# Maduino_Zero_Lorawan_Node_v1_0.net
KiCad netlist of a schematic drawn in EAGLE
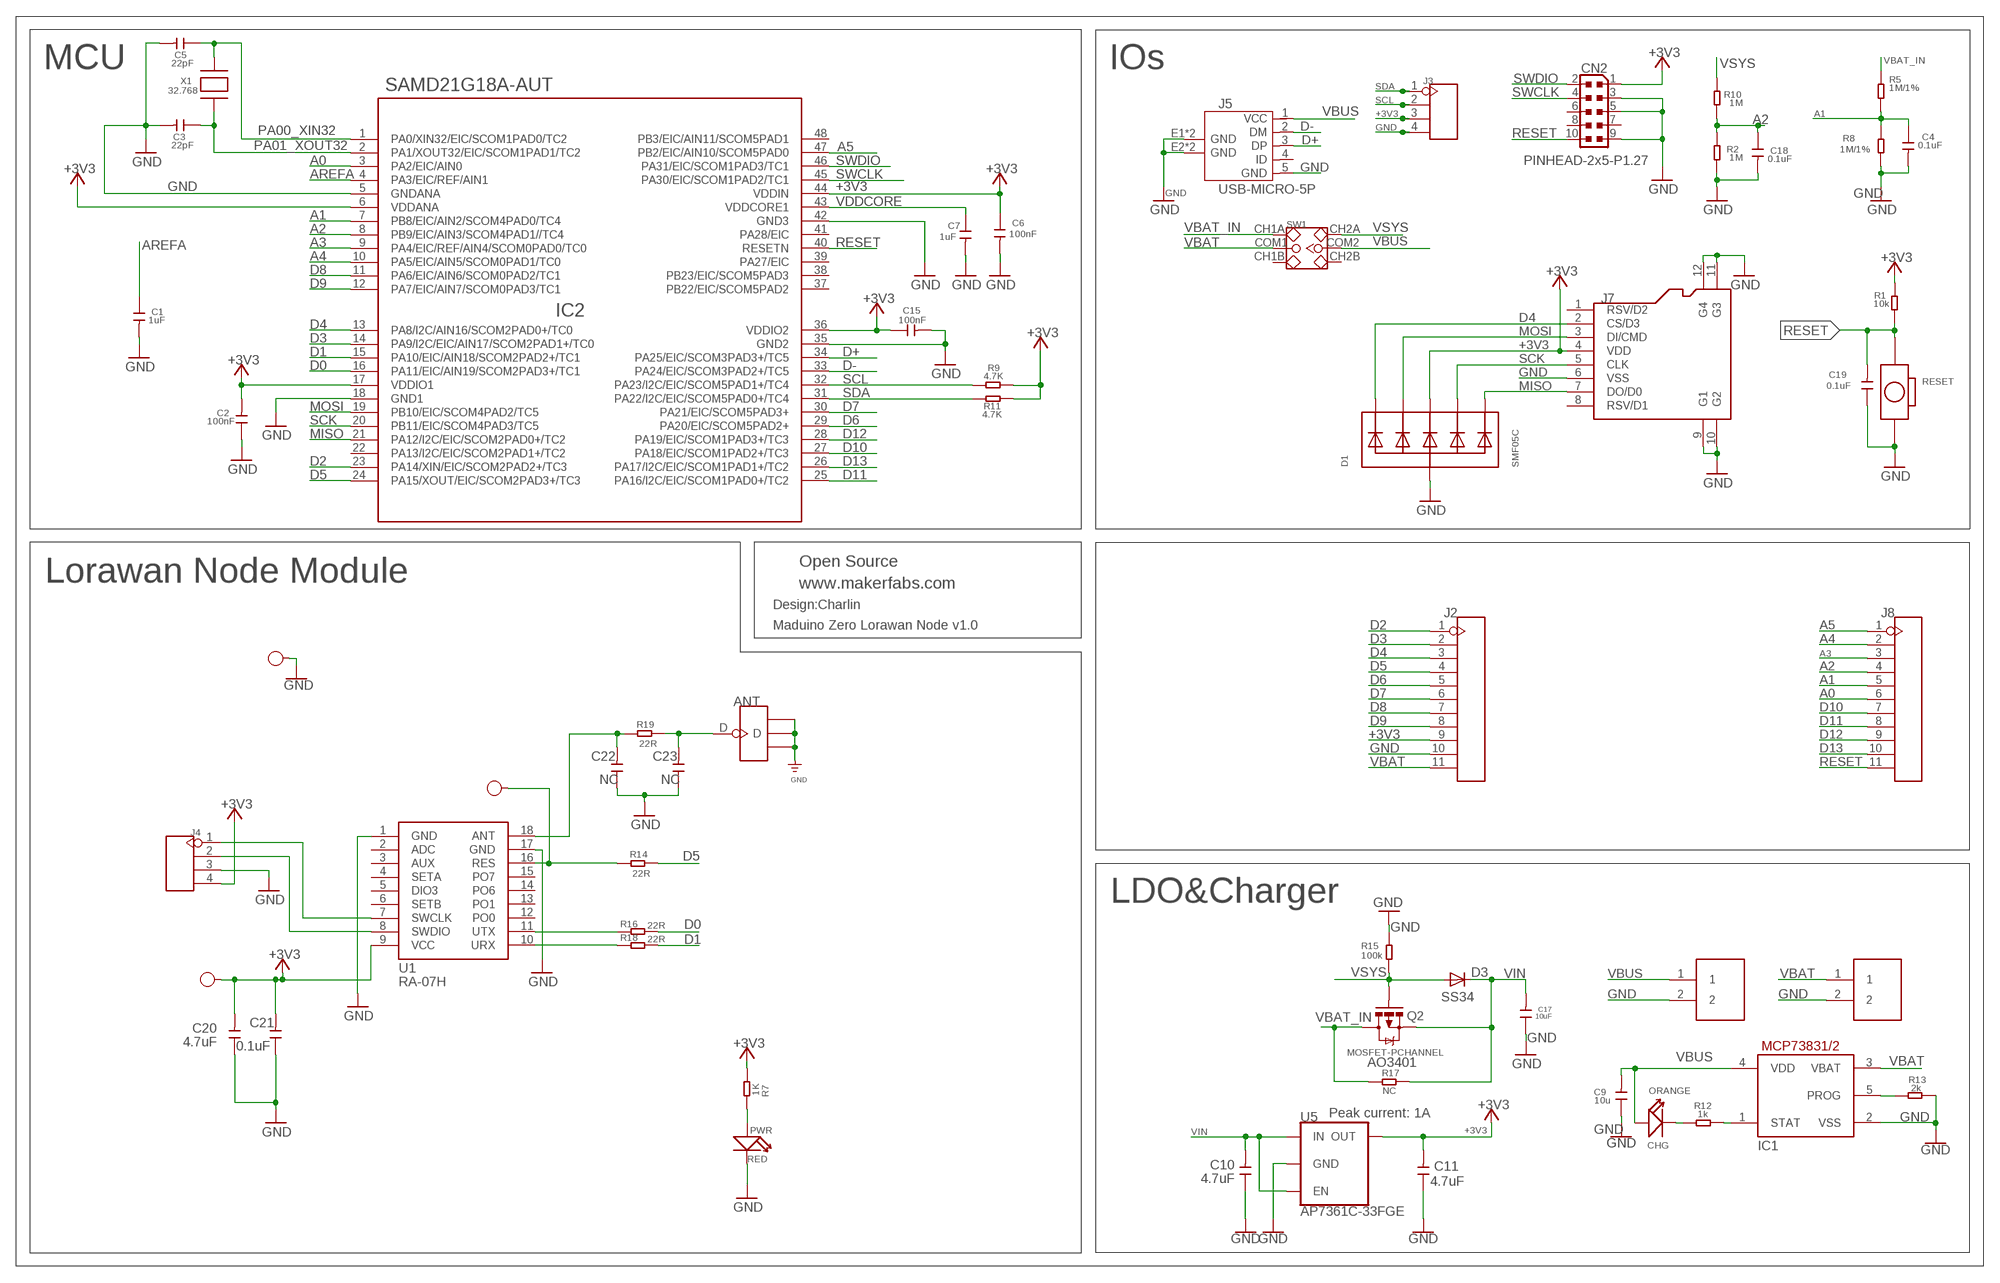
[diagram p0: schematic, sheet 1]

(export (version "E")
  (design (tool "Eeschema 10.0.6"))
  (components
    (comp (ref "3V3")
      (value "TEST-POINT'4545'")
      (footprint "eagle-import:TP-D45MIL")
      (fields (field (name "PARTNO") "DNP") (field (name "PARTNO_1") "DNP"))
      (libsource (lib "eagle-import") (part "TEST-POINT'4545'"))
    )
    (comp (ref "ANT")
      (value "ANTENNA-U-FL")
      (footprint "eagle-import:4P-U-FL")
      (libsource (lib "eagle-import") (part "ANTENNA-U-FL"))
    )
    (comp (ref "C1")
      (value "1uF")
      (footprint "eagle-import:C0603")
      (libsource (lib "eagle-import") (part "C-0603"))
    )
    (comp (ref "C2")
      (value "100nF")
      (footprint "eagle-import:C0603")
      (libsource (lib "eagle-import") (part "C-0603"))
    )
    (comp (ref "C3")
      (value "22pF")
      (footprint "eagle-import:C0603")
      (libsource (lib "eagle-import") (part "C-0603"))
    )
    (comp (ref "C4")
      (value "0.1uF")
      (footprint "eagle-import:C0603")
      (libsource (lib "eagle-import") (part "C-0603"))
    )
    (comp (ref "C5")
      (value "22pF")
      (footprint "eagle-import:C0603")
      (libsource (lib "eagle-import") (part "C-0603"))
    )
    (comp (ref "C6")
      (value "100nF")
      (footprint "eagle-import:C0603")
      (libsource (lib "eagle-import") (part "C-0603"))
    )
    (comp (ref "C7")
      (value "1uF")
      (footprint "eagle-import:C0603")
      (libsource (lib "eagle-import") (part "C-0603"))
    )
    (comp (ref "C9")
      (value "10u")
      (footprint "eagle-import:C0603")
      (libsource (lib "eagle-import") (part "C-0603"))
    )
    (comp (ref "C10")
      (value "4.7uF")
      (footprint "eagle-import:C0603")
      (libsource (lib "eagle-import") (part "C-0603"))
    )
    (comp (ref "C11")
      (value "4.7uF")
      (footprint "eagle-import:C0603")
      (libsource (lib "eagle-import") (part "C-0603"))
    )
    (comp (ref "C15")
      (value "100nF")
      (footprint "eagle-import:C0603")
      (libsource (lib "eagle-import") (part "C-0603"))
    )
    (comp (ref "C17")
      (value "10uF")
      (footprint "eagle-import:C0603")
      (libsource (lib "eagle-import") (part "C-0603"))
    )
    (comp (ref "C18")
      (value "0.1uF")
      (footprint "eagle-import:C0603")
      (libsource (lib "eagle-import") (part "C-0603"))
    )
    (comp (ref "C19")
      (value "0.1uF")
      (footprint "eagle-import:C0603")
      (libsource (lib "eagle-import") (part "C-0603"))
    )
    (comp (ref "C20")
      (value "4.7uF")
      (footprint "eagle-import:C0603")
      (libsource (lib "eagle-import") (part "C-0603"))
    )
    (comp (ref "C21")
      (value "0.1uF")
      (footprint "eagle-import:C0603")
      (libsource (lib "eagle-import") (part "C-0603"))
    )
    (comp (ref "C22")
      (value "NC")
      (footprint "eagle-import:C0603")
      (libsource (lib "eagle-import") (part "C-0603"))
    )
    (comp (ref "C23")
      (value "NC")
      (footprint "eagle-import:C0603")
      (libsource (lib "eagle-import") (part "C-0603"))
    )
    (comp (ref "CHG")
      (value "ORANGE")
      (footprint "eagle-import:D0603")
      (libsource (lib "eagle-import") (part "007-LED0603"))
    )
    (comp (ref "CN2")
      (value "PINHEAD-2x5-P1.27")
      (footprint "eagle-import:PINHEAD_2X05_127")
      (libsource (lib "eagle-import") (part "0171_PH127-205DF055G00AROUND-PADS"))
    )
    (comp (ref "D1")
      (value "SMF05C")
      (footprint "eagle-import:SOT363")
      (libsource (lib "eagle-import") (part "TVSARRAY_5LANE"))
    )
    (comp (ref "D3")
      (value "SS34")
      (footprint "eagle-import:DO-214AC")
      (libsource (lib "eagle-import") (part "DIODE-DO-214AC"))
    )
    (comp (ref "GND")
      (value "TEST-POINT'4545'")
      (footprint "eagle-import:TP-D45MIL")
      (fields (field (name "PARTNO") "DNP"))
      (libsource (lib "eagle-import") (part "TEST-POINT'4545'"))
    )
    (comp (ref "IC1")
      (value "MCP73831/OT")
      (footprint "eagle-import:SOT23-5L")
      (libsource (lib "eagle-import") (part "MCP73831/OT"))
    )
    (comp (ref "IC2")
      (value "SAMD21G18A-AUT")
      (footprint "eagle-import:TQFP48-7X7")
      (libsource (lib "eagle-import") (part "ATSAMD21G18A-AUT"))
    )
    (comp (ref "J1")
      (value "PH2.0-2P-90-DIP")
      (footprint "eagle-import:PH2.0-2P-90-DIP")
      (libsource (lib "eagle-import") (part "PH2.0-2P-90-DIP"))
    )
    (comp (ref "J2")
      (value "HEADER-11P-2.54")
      (footprint "eagle-import:11P-2.54")
      (libsource (lib "eagle-import") (part "HEADER-11P-2.54"))
    )
    (comp (ref "J3")
      (value "HEADER-4P-60/35MILROUND")
      (footprint "eagle-import:4P-65_35ROUND")
      (libsource (lib "eagle-import") (part "HEADER-4P-60/35MILROUND"))
    )
    (comp (ref "J4")
      (value "HEADER-4P-60/35MILROUND")
      (footprint "eagle-import:4P-65_35ROUND")
      (libsource (lib "eagle-import") (part "HEADER-4P-60/35MILROUND"))
    )
    (comp (ref "J5")
      (value "USB-MICRO-5P")
      (footprint "eagle-import:MICRO-USB-5P")
      (libsource (lib "eagle-import") (part "USB-MICRO-5P"))
    )
    (comp (ref "J6")
      (value "PH2.0-2P-90-DIP")
      (footprint "eagle-import:PH2.0-2P-90-DIP")
      (libsource (lib "eagle-import") (part "PH2.0-2P-90-DIP"))
    )
    (comp (ref "J7")
      (value "HOLDER-MICROSD-8P")
      (footprint "eagle-import:8P-SMD")
      (libsource (lib "eagle-import") (part "HOLDER-MICROSD-8P"))
    )
    (comp (ref "J8")
      (value "HEADER-11P-2.54")
      (footprint "eagle-import:11P-2.54")
      (libsource (lib "eagle-import") (part "HEADER-11P-2.54"))
    )
    (comp (ref "PWR")
      (value "RED")
      (footprint "eagle-import:LED-0603")
      (libsource (lib "eagle-import") (part "LED'0603'"))
    )
    (comp (ref "Q2")
      (value "MOSFET-PCHANNEL")
      (footprint "eagle-import:SOT23-3")
      (libsource (lib "eagle-import") (part "MOSFET-PCHANNEL"))
    )
    (comp (ref "R1")
      (value "10k")
      (footprint "eagle-import:R0603")
      (libsource (lib "eagle-import") (part "R-0603"))
    )
    (comp (ref "R2")
      (value "1M")
      (footprint "eagle-import:R0603")
      (libsource (lib "eagle-import") (part "R-0603"))
    )
    (comp (ref "R5")
      (value "1M/1%")
      (footprint "eagle-import:R0603")
      (libsource (lib "eagle-import") (part "R-0603"))
    )
    (comp (ref "R7")
      (value "1K")
      (footprint "eagle-import:R0603")
      (libsource (lib "eagle-import") (part "R-0603"))
    )
    (comp (ref "R8")
      (value "1M/1%")
      (footprint "eagle-import:R0603")
      (libsource (lib "eagle-import") (part "R-0603"))
    )
    (comp (ref "R9")
      (value "4.7K")
      (footprint "eagle-import:R0603")
      (libsource (lib "eagle-import") (part "R-0603"))
    )
    (comp (ref "R10")
      (value "1M")
      (footprint "eagle-import:R0603")
      (libsource (lib "eagle-import") (part "R-0603"))
    )
    (comp (ref "R11")
      (value "4.7K")
      (footprint "eagle-import:R0603")
      (libsource (lib "eagle-import") (part "R-0603"))
    )
    (comp (ref "R12")
      (value "1k")
      (footprint "eagle-import:R0603")
      (libsource (lib "eagle-import") (part "R-0603"))
    )
    (comp (ref "R13")
      (value "2k")
      (footprint "eagle-import:R0603")
      (libsource (lib "eagle-import") (part "R-0603"))
    )
    (comp (ref "R14")
      (value "22R")
      (footprint "eagle-import:R0603")
      (libsource (lib "eagle-import") (part "R-0603"))
    )
    (comp (ref "R15")
      (value "100k")
      (footprint "eagle-import:R0603")
      (libsource (lib "eagle-import") (part "R-0603"))
    )
    (comp (ref "R16")
      (value "22R")
      (footprint "eagle-import:R0603")
      (libsource (lib "eagle-import") (part "R-0603"))
    )
    (comp (ref "R17")
      (value "NC")
      (footprint "eagle-import:R0603")
      (libsource (lib "eagle-import") (part "R-0603"))
    )
    (comp (ref "R18")
      (value "22R")
      (footprint "eagle-import:R0603")
      (libsource (lib "eagle-import") (part "R-0603"))
    )
    (comp (ref "R19")
      (value "22R")
      (footprint "eagle-import:R0603")
      (libsource (lib "eagle-import") (part "R-0603"))
    )
    (comp (ref "RES")
      (value "TEST-POINT'4545'")
      (footprint "eagle-import:TP-D45MIL")
      (fields (field (name "PARTNO") "DNP") (field (name "PARTNO_1") "DNP"))
      (libsource (lib "eagle-import") (part "TEST-POINT'4545'"))
    )
    (comp (ref "RESET")
      (value "BOTTON-2P-90D")
      (footprint "eagle-import:2P-7.62X3.56-90D")
      (libsource (lib "eagle-import") (part "BOTTON-2P-90D"))
    )
    (comp (ref "SW1")
      (value "SWITCH-2CH-6P")
      (footprint "eagle-import:6P-2CH-2.54-7.6X3.0")
      (libsource (lib "eagle-import") (part "SWITCH-2CH-6P"))
    )
    (comp (ref "U1")
      (value "RA-07H")
      (footprint "eagle-import:SMD18-127P-1600L1600W")
      (libsource (lib "eagle-import") (part "RA-07H"))
    )
    (comp (ref "U5")
      (value "AP7361C-33FGE")
      (footprint "eagle-import:8-UDFN")
      (libsource (lib "eagle-import") (part "AP7361C-33FGE"))
    )
    (comp (ref "X1")
      (value "32.768")
      (footprint "eagle-import:XTAL3215")
      (libsource (lib "eagle-import") (part "XTAL-3.2X1.5"))
    )
  )
  (nets
    (net (code "1") (name "+3V3") (class "Default")
      (node (ref "3V3") (pin "T") (pinfunction "T_T") (pintype "bidirectional"))
      (node (ref "C11") (pin "2") (pinfunction "2_2") (pintype "passive"))
      (node (ref "C15") (pin "1") (pinfunction "1_1") (pintype "passive"))
      (node (ref "C2") (pin "2") (pinfunction "2_2") (pintype "passive"))
      (node (ref "C20") (pin "2") (pinfunction "2_2") (pintype "passive"))
      (node (ref "C21") (pin "2") (pinfunction "2_2") (pintype "passive"))
      (node (ref "C6") (pin "1") (pinfunction "1_1") (pintype "passive"))
      (node (ref "CN2") (pin "1") (pinfunction "1_1") (pintype "passive"))
      (node (ref "D1") (pin "4") (pinfunction "C3_4") (pintype "passive"))
      (node (ref "IC2") (pin "17") (pinfunction "VDDIO1_17") (pintype "power_in"))
      (node (ref "IC2") (pin "36") (pinfunction "VDDIO2_36") (pintype "power_in"))
      (node (ref "IC2") (pin "44") (pinfunction "VDDIN_44") (pintype "power_in"))
      (node (ref "IC2") (pin "6") (pinfunction "VDDANA_6") (pintype "power_in"))
      (node (ref "J2") (pin "9") (pinfunction "9_9") (pintype "bidirectional"))
      (node (ref "J3") (pin "3") (pinfunction "P$3_3") (pintype "bidirectional"))
      (node (ref "J4") (pin "4") (pinfunction "P$4_4") (pintype "bidirectional"))
      (node (ref "J7") (pin "4") (pinfunction "VDD_4") (pintype "bidirectional"))
      (node (ref "R1") (pin "2") (pinfunction "2_2") (pintype "passive"))
      (node (ref "R11") (pin "2") (pinfunction "2_2") (pintype "passive"))
      (node (ref "R7") (pin "1") (pinfunction "1_1") (pintype "passive"))
      (node (ref "R9") (pin "2") (pinfunction "2_2") (pintype "passive"))
      (node (ref "U1") (pin "9") (pinfunction "VCC_9") (pintype "bidirectional"))
      (node (ref "U5") (pin "1") (pinfunction "OUT_1") (pintype "output"))
    )
    (net (code "2") (name "/A0") (class "Default")
      (node (ref "IC2") (pin "3") (pinfunction "PA2/EIC/AIN0_3") (pintype "bidirectional"))
      (node (ref "J8") (pin "6") (pinfunction "6_6") (pintype "bidirectional"))
    )
    (net (code "3") (name "/A1") (class "Default")
      (node (ref "C4") (pin "1") (pinfunction "1_1") (pintype "passive"))
      (node (ref "IC2") (pin "7") (pinfunction "PB8/EIC/AIN2/SCOM4PAD0/TC4_7") (pintype "bidirectional"))
      (node (ref "J8") (pin "5") (pinfunction "5_5") (pintype "bidirectional"))
      (node (ref "R5") (pin "1") (pinfunction "1_1") (pintype "passive"))
      (node (ref "R8") (pin "2") (pinfunction "2_2") (pintype "passive"))
    )
    (net (code "4") (name "/A2") (class "Default")
      (node (ref "C18") (pin "1") (pinfunction "1_1") (pintype "passive"))
      (node (ref "IC2") (pin "8") (pinfunction "PB9/EIC/AIN3/SCOM4PAD1//TC4_8") (pintype "bidirectional"))
      (node (ref "J8") (pin "4") (pinfunction "4_4") (pintype "bidirectional"))
      (node (ref "R10") (pin "1") (pinfunction "1_1") (pintype "passive"))
      (node (ref "R2") (pin "2") (pinfunction "2_2") (pintype "passive"))
    )
    (net (code "5") (name "/A3") (class "Default")
      (node (ref "IC2") (pin "9") (pinfunction "PA4/EIC/REF/AIN4/SCOM0PAD0/TC0_9") (pintype "bidirectional"))
      (node (ref "J8") (pin "3") (pinfunction "3_3") (pintype "bidirectional"))
    )
    (net (code "6") (name "/A4") (class "Default")
      (node (ref "IC2") (pin "10") (pinfunction "PA5/EIC/AIN5/SCOM0PAD1/TC0_10") (pintype "bidirectional"))
      (node (ref "J8") (pin "2") (pinfunction "2_2") (pintype "bidirectional"))
    )
    (net (code "7") (name "/A5") (class "Default")
      (node (ref "IC2") (pin "47") (pinfunction "PB2/EIC/AIN10/SCOM5PAD0_47") (pintype "bidirectional"))
      (node (ref "J8") (pin "1") (pinfunction "1_1") (pintype "bidirectional"))
    )
    (net (code "8") (name "/AREFA") (class "Default")
      (node (ref "C1") (pin "1") (pinfunction "1_1") (pintype "passive"))
      (node (ref "IC2") (pin "4") (pinfunction "PA3/EIC/REF/AIN1_4") (pintype "bidirectional"))
    )
    (net (code "9") (name "/D+") (class "Default")
      (node (ref "IC2") (pin "34") (pinfunction "PA25/EIC/SCOM3PAD3+/TC5_34") (pintype "bidirectional"))
      (node (ref "J5") (pin "3") (pinfunction "DP_3") (pintype "bidirectional"))
    )
    (net (code "10") (name "/D-") (class "Default")
      (node (ref "IC2") (pin "33") (pinfunction "PA24/EIC/SCOM3PAD2+/TC5_33") (pintype "bidirectional"))
      (node (ref "J5") (pin "2") (pinfunction "DM_2") (pintype "bidirectional"))
    )
    (net (code "11") (name "/D0") (class "Default")
      (node (ref "IC2") (pin "16") (pinfunction "PA11/EIC/AIN19/SCOM2PAD3+/TC1_16") (pintype "bidirectional"))
      (node (ref "R16") (pin "2") (pinfunction "2_2") (pintype "passive"))
    )
    (net (code "12") (name "/D1") (class "Default")
      (node (ref "IC2") (pin "15") (pinfunction "PA10/EIC/AIN18/SCOM2PAD2+/TC1_15") (pintype "bidirectional"))
      (node (ref "R18") (pin "2") (pinfunction "2_2") (pintype "passive"))
    )
    (net (code "13") (name "/D2") (class "Default")
      (node (ref "IC2") (pin "23") (pinfunction "PA14/XIN/EIC/SCOM2PAD2+/TC3_23") (pintype "bidirectional"))
      (node (ref "J2") (pin "1") (pinfunction "1_1") (pintype "bidirectional"))
    )
    (net (code "14") (name "/D3") (class "Default")
      (node (ref "IC2") (pin "14") (pinfunction "PA9/I2C/EIC/AIN17/SCOM2PAD1+/TC0_14") (pintype "bidirectional"))
      (node (ref "J2") (pin "2") (pinfunction "2_2") (pintype "bidirectional"))
    )
    (net (code "15") (name "/D4") (class "Default")
      (node (ref "D1") (pin "1") (pinfunction "C1_1") (pintype "passive"))
      (node (ref "IC2") (pin "13") (pinfunction "PA8/I2C/AIN16/SCOM2PAD0+/TC0_13") (pintype "bidirectional"))
      (node (ref "J2") (pin "3") (pinfunction "3_3") (pintype "bidirectional"))
      (node (ref "J7") (pin "2") (pinfunction "CS/D3_2") (pintype "bidirectional"))
    )
    (net (code "16") (name "/D5") (class "Default")
      (node (ref "IC2") (pin "24") (pinfunction "PA15/XOUT/EIC/SCOM2PAD3+/TC3_24") (pintype "bidirectional"))
      (node (ref "J2") (pin "4") (pinfunction "4_4") (pintype "bidirectional"))
      (node (ref "R14") (pin "2") (pinfunction "2_2") (pintype "passive"))
    )
    (net (code "17") (name "/D6") (class "Default")
      (node (ref "IC2") (pin "29") (pinfunction "PA20/EIC/SCOM5PAD2+_29") (pintype "bidirectional"))
      (node (ref "J2") (pin "5") (pinfunction "5_5") (pintype "bidirectional"))
    )
    (net (code "18") (name "/D7") (class "Default")
      (node (ref "IC2") (pin "30") (pinfunction "PA21/EIC/SCOM5PAD3+_30") (pintype "bidirectional"))
      (node (ref "J2") (pin "6") (pinfunction "6_6") (pintype "bidirectional"))
    )
    (net (code "19") (name "/D8") (class "Default")
      (node (ref "IC2") (pin "11") (pinfunction "PA6/EIC/AIN6/SCOM0PAD2/TC1_11") (pintype "bidirectional"))
      (node (ref "J2") (pin "7") (pinfunction "7_7") (pintype "bidirectional"))
    )
    (net (code "20") (name "/D9") (class "Default")
      (node (ref "IC2") (pin "12") (pinfunction "PA7/EIC/AIN7/SCOM0PAD3/TC1_12") (pintype "bidirectional"))
      (node (ref "J2") (pin "8") (pinfunction "8_8") (pintype "bidirectional"))
    )
    (net (code "21") (name "/D10") (class "Default")
      (node (ref "IC2") (pin "27") (pinfunction "PA18/EIC/SCOM1PAD2+/TC3_27") (pintype "bidirectional"))
      (node (ref "J8") (pin "7") (pinfunction "7_7") (pintype "bidirectional"))
    )
    (net (code "22") (name "/D11") (class "Default")
      (node (ref "IC2") (pin "25") (pinfunction "PA16/I2C/EIC/SCOM1PAD0+/TC2_25") (pintype "bidirectional"))
      (node (ref "J8") (pin "8") (pinfunction "8_8") (pintype "bidirectional"))
    )
    (net (code "23") (name "/D12") (class "Default")
      (node (ref "IC2") (pin "28") (pinfunction "PA19/EIC/SCOM1PAD3+/TC3_28") (pintype "bidirectional"))
      (node (ref "J8") (pin "9") (pinfunction "9_9") (pintype "bidirectional"))
    )
    (net (code "24") (name "/D13") (class "Default")
      (node (ref "IC2") (pin "26") (pinfunction "PA17/I2C/EIC/SCOM1PAD1+/TC2_26") (pintype "bidirectional"))
      (node (ref "J8") (pin "10") (pinfunction "10_10") (pintype "bidirectional"))
    )
    (net (code "25") (name "/MISO") (class "Default")
      (node (ref "D1") (pin "6") (pinfunction "C5_6") (pintype "passive"))
      (node (ref "IC2") (pin "21") (pinfunction "PA12/I2C/EIC/SCOM2PAD0+/TC2_21") (pintype "bidirectional"))
      (node (ref "J7") (pin "7") (pinfunction "DO/D0_7") (pintype "bidirectional"))
    )
    (net (code "26") (name "/MOSI") (class "Default")
      (node (ref "D1") (pin "3") (pinfunction "C2_3") (pintype "passive"))
      (node (ref "IC2") (pin "19") (pinfunction "PB10/EIC/SCOM4PAD2/TC5_19") (pintype "bidirectional"))
      (node (ref "J7") (pin "3") (pinfunction "DI/CMD_3") (pintype "bidirectional"))
    )
    (net (code "27") (name "/PA00_XIN32") (class "Default")
      (node (ref "C5") (pin "1") (pinfunction "1_1") (pintype "passive"))
      (node (ref "IC2") (pin "1") (pinfunction "PA0/XIN32/EIC/SCOM1PAD0/TC2_1") (pintype "bidirectional"))
      (node (ref "X1") (pin "P$2") (pinfunction "P$2_P$2") (pintype "bidirectional"))
    )
    (net (code "28") (name "/PA01_XOUT32") (class "Default")
      (node (ref "C3") (pin "1") (pinfunction "1_1") (pintype "passive"))
      (node (ref "IC2") (pin "2") (pinfunction "PA1/XOUT32/EIC/SCOM1PAD1/TC2_2") (pintype "bidirectional"))
      (node (ref "X1") (pin "P$1") (pinfunction "P$1_P$1") (pintype "bidirectional"))
    )
    (net (code "29") (name "/SCK") (class "Default")
      (node (ref "D1") (pin "5") (pinfunction "C4_5") (pintype "passive"))
      (node (ref "IC2") (pin "20") (pinfunction "PB11/EIC/SCOM4PAD3/TC5_20") (pintype "bidirectional"))
      (node (ref "J7") (pin "5") (pinfunction "CLK_5") (pintype "bidirectional"))
    )
    (net (code "30") (name "/SCL") (class "Default")
      (node (ref "IC2") (pin "32") (pinfunction "PA23/I2C/EIC/SCOM5PAD1+/TC4_32") (pintype "bidirectional"))
      (node (ref "J3") (pin "2") (pinfunction "P$2_2") (pintype "bidirectional"))
      (node (ref "R9") (pin "1") (pinfunction "1_1") (pintype "passive"))
    )
    (net (code "31") (name "/SDA") (class "Default")
      (node (ref "IC2") (pin "31") (pinfunction "PA22/I2C/EIC/SCOM5PAD0+/TC4_31") (pintype "bidirectional"))
      (node (ref "J3") (pin "1") (pinfunction "P$1_1") (pintype "bidirectional"))
      (node (ref "R11") (pin "1") (pinfunction "1_1") (pintype "passive"))
    )
    (net (code "32") (name "/SWCLK") (class "Default")
      (node (ref "CN2") (pin "4") (pinfunction "4_4") (pintype "passive"))
      (node (ref "IC2") (pin "45") (pinfunction "PA30/EIC/SCOM1PAD2/TC1_45") (pintype "bidirectional"))
    )
    (net (code "33") (name "/SWDIO") (class "Default")
      (node (ref "CN2") (pin "2") (pinfunction "2_2") (pintype "passive"))
      (node (ref "IC2") (pin "46") (pinfunction "PA31/EIC/SCOM1PAD3/TC1_46") (pintype "bidirectional"))
    )
    (net (code "34") (name "/VBAT") (class "Default")
      (node (ref "IC1") (pin "3") (pinfunction "VBAT_3") (pintype "bidirectional"))
      (node (ref "J2") (pin "11") (pinfunction "11_11") (pintype "bidirectional"))
      (node (ref "J6") (pin "1") (pinfunction "1_1") (pintype "bidirectional"))
      (node (ref "SW1") (pin "COM1") (pinfunction "COM1_COM1") (pintype "bidirectional"))
    )
    (net (code "35") (name "/VBAT_IN") (class "Default")
      (node (ref "Q2") (pin "3") (pinfunction "D_3") (pintype "passive"))
      (node (ref "R17") (pin "1") (pinfunction "1_1") (pintype "passive"))
      (node (ref "R5") (pin "2") (pinfunction "2_2") (pintype "passive"))
      (node (ref "SW1") (pin "CH1A") (pinfunction "CH1A_CH1A") (pintype "bidirectional"))
    )
    (net (code "36") (name "/VBUS") (class "Default")
      (node (ref "C9") (pin "2") (pinfunction "2_2") (pintype "passive"))
      (node (ref "CHG") (pin "+") (pinfunction "+_+") (pintype "passive"))
      (node (ref "IC1") (pin "4") (pinfunction "VDD_4") (pintype "power_in"))
      (node (ref "J1") (pin "1") (pinfunction "1_1") (pintype "bidirectional"))
      (node (ref "J5") (pin "1") (pinfunction "VCC_1") (pintype "bidirectional"))
      (node (ref "SW1") (pin "COM2") (pinfunction "COM2_COM2") (pintype "bidirectional"))
    )
    (net (code "37") (name "/VDDCORE") (class "Default")
      (node (ref "C7") (pin "1") (pinfunction "1_1") (pintype "passive"))
      (node (ref "IC2") (pin "43") (pinfunction "VDDCORE1_43") (pintype "input"))
    )
    (net (code "38") (name "/VIN") (class "Default")
      (node (ref "C10") (pin "2") (pinfunction "2_2") (pintype "passive"))
      (node (ref "C17") (pin "2") (pinfunction "2_2") (pintype "passive"))
      (node (ref "D3") (pin "C") (pinfunction "C_C") (pintype "passive"))
      (node (ref "Q2") (pin "2") (pinfunction "S_2") (pintype "passive"))
      (node (ref "R17") (pin "2") (pinfunction "2_2") (pintype "passive"))
      (node (ref "U5") (pin "5") (pinfunction "EN_5") (pintype "bidirectional"))
      (node (ref "U5") (pin "8") (pinfunction "IN_8") (pintype "input"))
    )
    (net (code "39") (name "/VSYS") (class "Default")
      (node (ref "D3") (pin "A") (pinfunction "A_A") (pintype "passive"))
      (node (ref "Q2") (pin "1") (pinfunction "G_1") (pintype "passive"))
      (node (ref "R10") (pin "2") (pinfunction "2_2") (pintype "passive"))
      (node (ref "R15") (pin "1") (pinfunction "1_1") (pintype "passive"))
      (node (ref "SW1") (pin "CH2A") (pinfunction "CH2A_CH2A") (pintype "bidirectional"))
    )
    (net (code "40") (name "GND") (class "Default")
      (node (ref "ANT") (pin "GND1") (pinfunction "GND1_GND1") (pintype "bidirectional"))
      (node (ref "ANT") (pin "GND2") (pinfunction "GND2_GND2") (pintype "bidirectional"))
      (node (ref "ANT") (pin "GND3") (pinfunction "GND3_GND3") (pintype "bidirectional"))
      (node (ref "C1") (pin "2") (pinfunction "2_2") (pintype "passive"))
      (node (ref "C10") (pin "1") (pinfunction "1_1") (pintype "passive"))
      (node (ref "C11") (pin "1") (pinfunction "1_1") (pintype "passive"))
      (node (ref "C15") (pin "2") (pinfunction "2_2") (pintype "passive"))
      (node (ref "C17") (pin "1") (pinfunction "1_1") (pintype "passive"))
      (node (ref "C18") (pin "2") (pinfunction "2_2") (pintype "passive"))
      (node (ref "C19") (pin "1") (pinfunction "1_1") (pintype "passive"))
      (node (ref "C2") (pin "1") (pinfunction "1_1") (pintype "passive"))
      (node (ref "C20") (pin "1") (pinfunction "1_1") (pintype "passive"))
      (node (ref "C21") (pin "1") (pinfunction "1_1") (pintype "passive"))
      (node (ref "C22") (pin "1") (pinfunction "1_1") (pintype "passive"))
      (node (ref "C23") (pin "1") (pinfunction "1_1") (pintype "passive"))
      (node (ref "C3") (pin "2") (pinfunction "2_2") (pintype "passive"))
      (node (ref "C4") (pin "2") (pinfunction "2_2") (pintype "passive"))
      (node (ref "C5") (pin "2") (pinfunction "2_2") (pintype "passive"))
      (node (ref "C6") (pin "2") (pinfunction "2_2") (pintype "passive"))
      (node (ref "C7") (pin "2") (pinfunction "2_2") (pintype "passive"))
      (node (ref "C9") (pin "1") (pinfunction "1_1") (pintype "passive"))
      (node (ref "CN2") (pin "3") (pinfunction "3_3") (pintype "passive"))
      (node (ref "CN2") (pin "5") (pinfunction "5_5") (pintype "passive"))
      (node (ref "CN2") (pin "9") (pinfunction "9_9") (pintype "passive"))
      (node (ref "D1") (pin "2") (pinfunction "A_2") (pintype "passive"))
      (node (ref "GND") (pin "T") (pinfunction "T_T") (pintype "bidirectional"))
      (node (ref "IC1") (pin "2") (pinfunction "VSS_2") (pintype "power_in"))
      (node (ref "IC2") (pin "18") (pinfunction "GND1_18") (pintype "power_in"))
      (node (ref "IC2") (pin "35") (pinfunction "GND2_35") (pintype "power_in"))
      (node (ref "IC2") (pin "42") (pinfunction "GND3_42") (pintype "power_in"))
      (node (ref "IC2") (pin "5") (pinfunction "GNDANA_5") (pintype "power_in"))
      (node (ref "J1") (pin "2") (pinfunction "2_2") (pintype "bidirectional"))
      (node (ref "J2") (pin "10") (pinfunction "10_10") (pintype "bidirectional"))
      (node (ref "J3") (pin "4") (pinfunction "P$4_4") (pintype "bidirectional"))
      (node (ref "J4") (pin "3") (pinfunction "P$3_3") (pintype "bidirectional"))
      (node (ref "J5") (pin "5") (pinfunction "GND_5") (pintype "bidirectional"))
      (node (ref "J5") (pin "E1") (pinfunction "GND_E1") (pintype "bidirectional"))
      (node (ref "J5") (pin "E2") (pinfunction "GND_E2") (pintype "bidirectional"))
      (node (ref "J5") (pin "P1") (pinfunction "GND_P1") (pintype "bidirectional"))
      (node (ref "J5") (pin "P2") (pinfunction "GND_P2") (pintype "bidirectional"))
      (node (ref "J6") (pin "2") (pinfunction "2_2") (pintype "bidirectional"))
      (node (ref "J7") (pin "10") (pinfunction "G2_10") (pintype "bidirectional"))
      (node (ref "J7") (pin "11") (pinfunction "G3_11") (pintype "bidirectional"))
      (node (ref "J7") (pin "12") (pinfunction "G4_12") (pintype "bidirectional"))
      (node (ref "J7") (pin "6") (pinfunction "VSS_6") (pintype "bidirectional"))
      (node (ref "J7") (pin "9") (pinfunction "G1_9") (pintype "bidirectional"))
      (node (ref "PWR") (pin "-") (pinfunction "-_-") (pintype "passive"))
      (node (ref "R13") (pin "2") (pinfunction "2_2") (pintype "passive"))
      (node (ref "R15") (pin "2") (pinfunction "2_2") (pintype "passive"))
      (node (ref "R2") (pin "1") (pinfunction "1_1") (pintype "passive"))
      (node (ref "R8") (pin "1") (pinfunction "1_1") (pintype "passive"))
      (node (ref "RESET") (pin "P$2") (pinfunction "2_P$2") (pintype "bidirectional"))
      (node (ref "U1") (pin "1") (pinfunction "GND_1") (pintype "bidirectional"))
      (node (ref "U1") (pin "17") (pinfunction "GND_17") (pintype "bidirectional"))
      (node (ref "U5") (pin "4") (pinfunction "GND_4") (pintype "input"))
      (node (ref "U5") (pin "EP") (pinfunction "GND_EP") (pintype "input"))
    )
    (net (code "41") (name "Net-(ANT-PadD)") (class "Default")
      (node (ref "ANT") (pin "D") (pinfunction "D_D") (pintype "bidirectional"))
      (node (ref "C23") (pin "2") (pinfunction "2_2") (pintype "passive"))
      (node (ref "R19") (pin "2") (pinfunction "2_2") (pintype "passive"))
    )
    (net (code "42") (name "Net-(CHG-Pad-)") (class "Default")
      (node (ref "CHG") (pin "-") (pinfunction "-_-") (pintype "passive"))
      (node (ref "R12") (pin "1") (pinfunction "1_1") (pintype "passive"))
    )
    (net (code "43") (name "Net-(IC1-PROG)") (class "Default")
      (node (ref "IC1") (pin "5") (pinfunction "PROG_5") (pintype "input"))
      (node (ref "R13") (pin "1") (pinfunction "1_1") (pintype "passive"))
    )
    (net (code "44") (name "Net-(IC1-STAT)") (class "Default")
      (node (ref "IC1") (pin "1") (pinfunction "STAT_1") (pintype "output"))
      (node (ref "R12") (pin "2") (pinfunction "2_2") (pintype "passive"))
    )
    (net (code "45") (name "Net-(J4-P$1)") (class "Default")
      (node (ref "J4") (pin "1") (pinfunction "P$1_1") (pintype "bidirectional"))
      (node (ref "U1") (pin "7") (pinfunction "SWCLK_7") (pintype "bidirectional"))
    )
    (net (code "46") (name "Net-(J4-P$2)") (class "Default")
      (node (ref "J4") (pin "2") (pinfunction "P$2_2") (pintype "bidirectional"))
      (node (ref "U1") (pin "8") (pinfunction "SWDIO_8") (pintype "bidirectional"))
    )
    (net (code "47") (name "Net-(PWR-Pad+)") (class "Default")
      (node (ref "PWR") (pin "+") (pinfunction "+_+") (pintype "passive"))
      (node (ref "R7") (pin "2") (pinfunction "2_2") (pintype "passive"))
    )
    (net (code "48") (name "Net-(U1-ANT)") (class "Default")
      (node (ref "C22") (pin "2") (pinfunction "2_2") (pintype "passive"))
      (node (ref "R19") (pin "1") (pinfunction "1_1") (pintype "passive"))
      (node (ref "U1") (pin "18") (pinfunction "ANT_18") (pintype "bidirectional"))
    )
    (net (code "49") (name "Net-(U1-RES)") (class "Default")
      (node (ref "R14") (pin "1") (pinfunction "1_1") (pintype "passive"))
      (node (ref "RES") (pin "T") (pinfunction "T_T") (pintype "bidirectional"))
      (node (ref "U1") (pin "16") (pinfunction "RES_16") (pintype "bidirectional"))
    )
    (net (code "50") (name "Net-(U1-URX)") (class "Default")
      (node (ref "R18") (pin "1") (pinfunction "1_1") (pintype "passive"))
      (node (ref "U1") (pin "10") (pinfunction "URX_10") (pintype "bidirectional"))
    )
    (net (code "51") (name "Net-(U1-UTX)") (class "Default")
      (node (ref "R16") (pin "1") (pinfunction "1_1") (pintype "passive"))
      (node (ref "U1") (pin "11") (pinfunction "UTX_11") (pintype "bidirectional"))
    )
    (net (code "52") (name "RESET") (class "Default")
      (node (ref "C19") (pin "2") (pinfunction "2_2") (pintype "passive"))
      (node (ref "CN2") (pin "10") (pinfunction "10_10") (pintype "passive"))
      (node (ref "IC2") (pin "40") (pinfunction "RESETN_40") (pintype "bidirectional"))
      (node (ref "J8") (pin "11") (pinfunction "11_11") (pintype "bidirectional"))
      (node (ref "R1") (pin "1") (pinfunction "1_1") (pintype "passive"))
      (node (ref "RESET") (pin "P$1") (pinfunction "1_P$1") (pintype "bidirectional"))
    )
    (net (code "53") (name "unconnected-(CN2-Pad6)") (class "Default")
      (node (ref "CN2") (pin "6") (pinfunction "6_6") (pintype "passive"))
    )
    (net (code "54") (name "unconnected-(CN2-Pad7)") (class "Default")
      (node (ref "CN2") (pin "7") (pinfunction "7_7") (pintype "passive"))
    )
    (net (code "55") (name "unconnected-(CN2-Pad8)") (class "Default")
      (node (ref "CN2") (pin "8") (pinfunction "8_8") (pintype "passive"))
    )
    (net (code "56") (name "unconnected-(IC2-PA13{slash}I2C{slash}EIC{slash}SCOM2PAD1+{slash}TC2-Pad22)") (class "Default")
      (node (ref "IC2") (pin "22") (pinfunction "PA13/I2C/EIC/SCOM2PAD1+/TC2_22") (pintype "bidirectional"))
    )
    (net (code "57") (name "unconnected-(IC2-PA27{slash}EIC-Pad39)") (class "Default")
      (node (ref "IC2") (pin "39") (pinfunction "PA27/EIC_39") (pintype "bidirectional"))
    )
    (net (code "58") (name "unconnected-(IC2-PA28{slash}EIC-Pad41)") (class "Default")
      (node (ref "IC2") (pin "41") (pinfunction "PA28/EIC_41") (pintype "bidirectional"))
    )
    (net (code "59") (name "unconnected-(IC2-PB3{slash}EIC{slash}AIN11{slash}SCOM5PAD1-Pad48)") (class "Default")
      (node (ref "IC2") (pin "48") (pinfunction "PB3/EIC/AIN11/SCOM5PAD1_48") (pintype "bidirectional"))
    )
    (net (code "60") (name "unconnected-(IC2-PB22{slash}EIC{slash}SCOM5PAD2-Pad37)") (class "Default")
      (node (ref "IC2") (pin "37") (pinfunction "PB22/EIC/SCOM5PAD2_37") (pintype "bidirectional"))
    )
    (net (code "61") (name "unconnected-(IC2-PB23{slash}EIC{slash}SCOM5PAD3-Pad38)") (class "Default")
      (node (ref "IC2") (pin "38") (pinfunction "PB23/EIC/SCOM5PAD3_38") (pintype "bidirectional"))
    )
    (net (code "62") (name "unconnected-(J5-ID-Pad4)") (class "Default")
      (node (ref "J5") (pin "4") (pinfunction "ID_4") (pintype "bidirectional"))
    )
    (net (code "63") (name "unconnected-(J7-RSV{slash}D1-Pad8)") (class "Default")
      (node (ref "J7") (pin "8") (pinfunction "RSV/D1_8") (pintype "bidirectional"))
    )
    (net (code "64") (name "unconnected-(J7-RSV{slash}D2-Pad1)") (class "Default")
      (node (ref "J7") (pin "1") (pinfunction "RSV/D2_1") (pintype "bidirectional"))
    )
    (net (code "65") (name "unconnected-(SW1-PadCH1B)") (class "Default")
      (node (ref "SW1") (pin "CH1B") (pinfunction "CH1B_CH1B") (pintype "bidirectional"))
    )
    (net (code "66") (name "unconnected-(SW1-PadCH2B)") (class "Default")
      (node (ref "SW1") (pin "CH2B") (pinfunction "CH2B_CH2B") (pintype "bidirectional"))
    )
    (net (code "67") (name "unconnected-(U1-ADC-Pad2)") (class "Default")
      (node (ref "U1") (pin "2") (pinfunction "ADC_2") (pintype "bidirectional"))
    )
    (net (code "68") (name "unconnected-(U1-AUX-Pad3)") (class "Default")
      (node (ref "U1") (pin "3") (pinfunction "AUX_3") (pintype "bidirectional"))
    )
    (net (code "69") (name "unconnected-(U1-DIO3-Pad5)") (class "Default")
      (node (ref "U1") (pin "5") (pinfunction "DIO3_5") (pintype "bidirectional"))
    )
    (net (code "70") (name "unconnected-(U1-PO0-Pad12)") (class "Default")
      (node (ref "U1") (pin "12") (pinfunction "PO0_12") (pintype "bidirectional"))
    )
    (net (code "71") (name "unconnected-(U1-PO1-Pad13)") (class "Default")
      (node (ref "U1") (pin "13") (pinfunction "PO1_13") (pintype "bidirectional"))
    )
    (net (code "72") (name "unconnected-(U1-PO6-Pad14)") (class "Default")
      (node (ref "U1") (pin "14") (pinfunction "PO6_14") (pintype "bidirectional"))
    )
    (net (code "73") (name "unconnected-(U1-PO7-Pad15)") (class "Default")
      (node (ref "U1") (pin "15") (pinfunction "PO7_15") (pintype "bidirectional"))
    )
    (net (code "74") (name "unconnected-(U1-SETA-Pad4)") (class "Default")
      (node (ref "U1") (pin "4") (pinfunction "SETA_4") (pintype "bidirectional"))
    )
    (net (code "75") (name "unconnected-(U1-SETB-Pad6)") (class "Default")
      (node (ref "U1") (pin "6") (pinfunction "SETB_6") (pintype "bidirectional"))
    )
  )
)
